# Adafruit_1_3in_128x64_STEMMA_QT.net
KiCad netlist of a schematic drawn in EAGLE
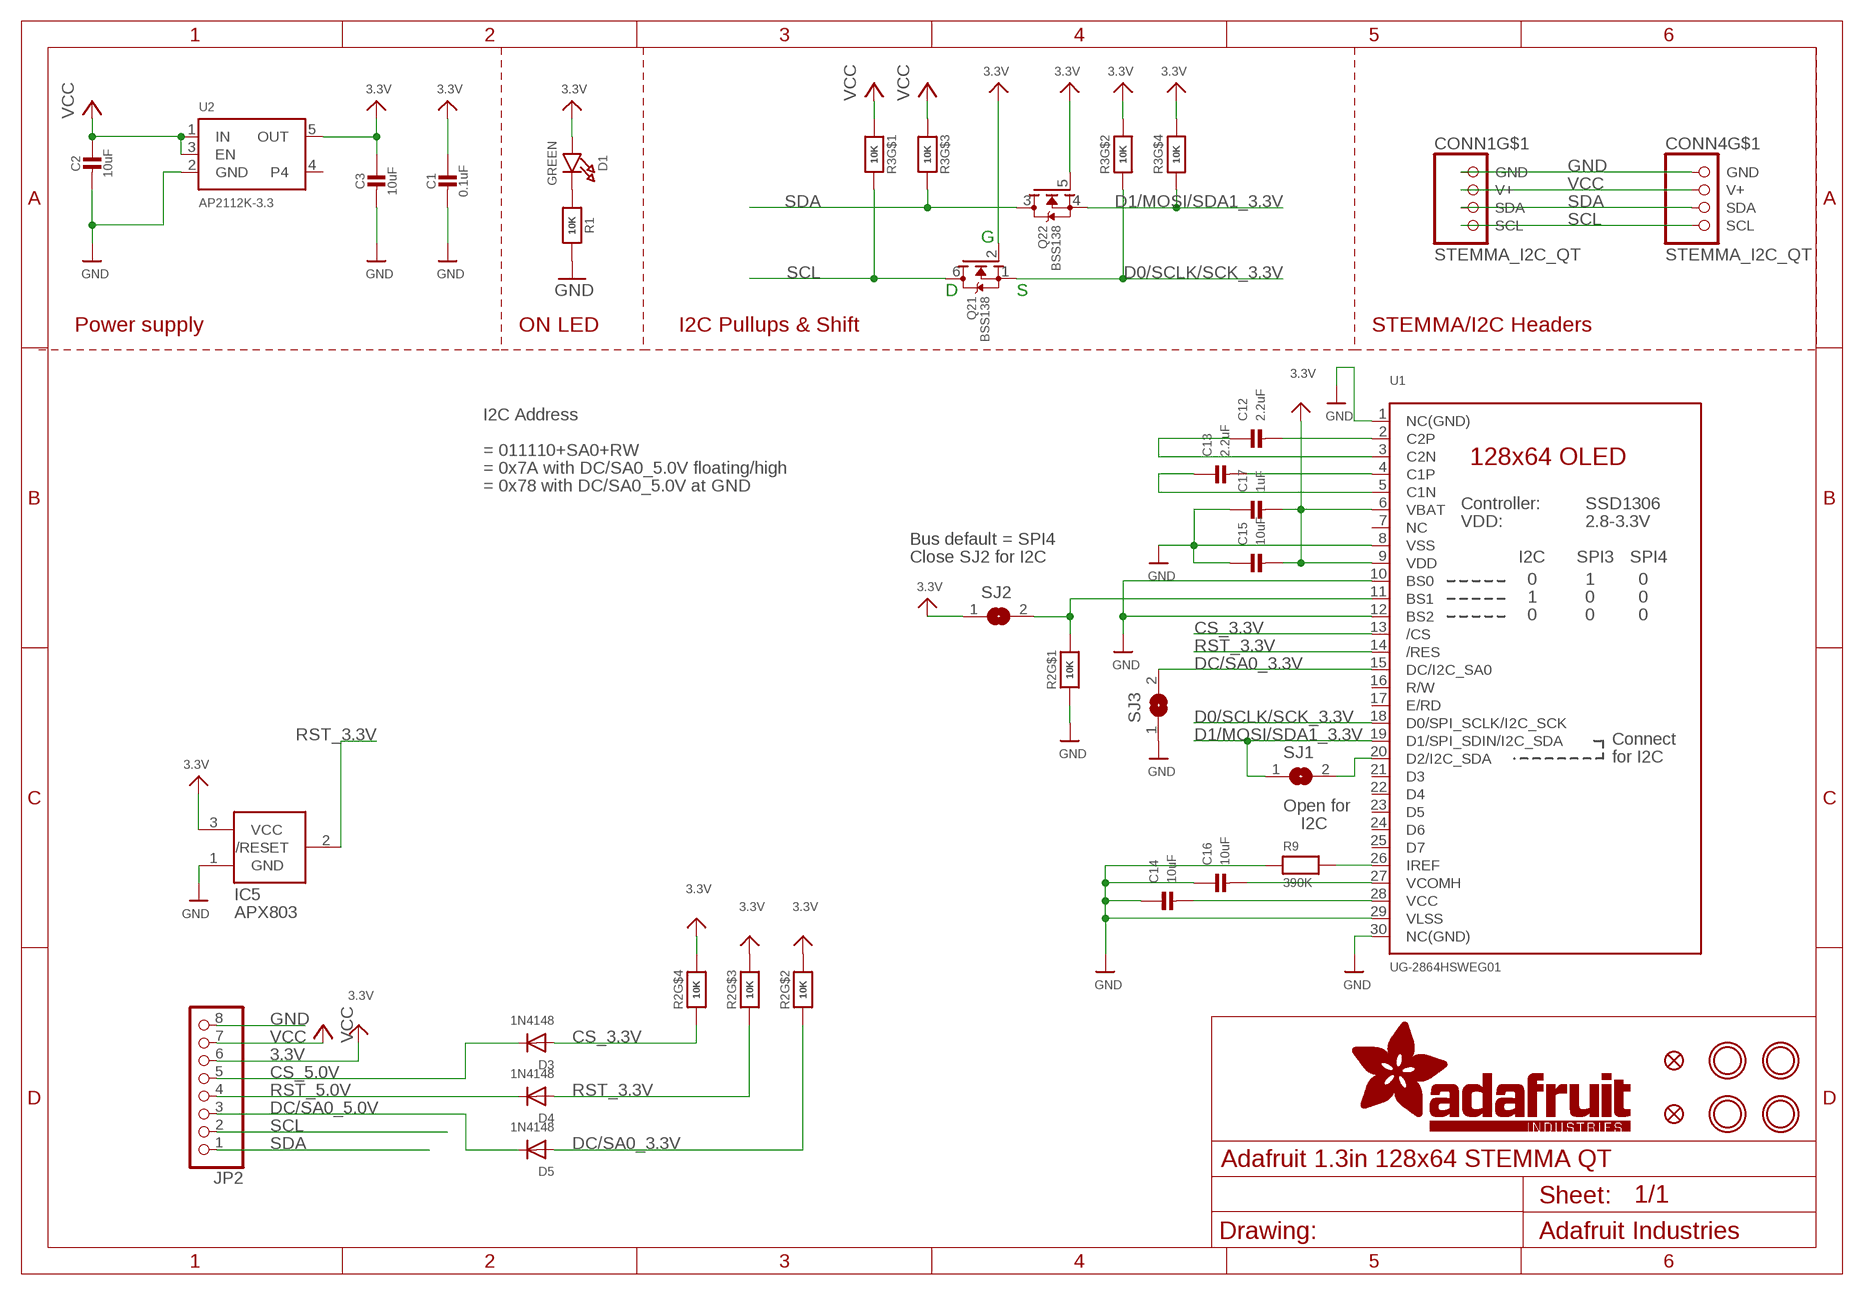
[diagram p0: schematic, sheet 1]

(export (version "E")
  (design (tool "Eeschema 10.0.6"))
  (components
    (comp (ref "C1")
      (value "0.1uF")
      (footprint "eagle-import:0603-NO")
      (libsource (lib "eagle-import") (part "CAP_CERAMIC0603_NO"))
    )
    (comp (ref "C2")
      (value "10uF")
      (footprint "eagle-import:0805-NO")
      (libsource (lib "eagle-import") (part "CAP_CERAMIC0805-NOOUTLINE"))
    )
    (comp (ref "C3")
      (value "10uF")
      (footprint "eagle-import:0805-NO")
      (libsource (lib "eagle-import") (part "CAP_CERAMIC0805-NOOUTLINE"))
    )
    (comp (ref "C12")
      (value "2.2uF")
      (footprint "eagle-import:0805-NO")
      (libsource (lib "eagle-import") (part "CAP_CERAMIC0805-NOOUTLINE"))
    )
    (comp (ref "C13")
      (value "2.2uF")
      (footprint "eagle-import:0805-NO")
      (libsource (lib "eagle-import") (part "CAP_CERAMIC0805-NOOUTLINE"))
    )
    (comp (ref "C14")
      (value "10uF")
      (footprint "eagle-import:0805-NO")
      (libsource (lib "eagle-import") (part "CAP_CERAMIC0805-NOOUTLINE"))
    )
    (comp (ref "C15")
      (value "10uF")
      (footprint "eagle-import:0805-NO")
      (libsource (lib "eagle-import") (part "CAP_CERAMIC0805-NOOUTLINE"))
    )
    (comp (ref "C16")
      (value "10uF")
      (footprint "eagle-import:0805-NO")
      (libsource (lib "eagle-import") (part "CAP_CERAMIC0805-NOOUTLINE"))
    )
    (comp (ref "C17")
      (value "1uF")
      (footprint "eagle-import:0603-NO")
      (libsource (lib "eagle-import") (part "CAP_CERAMIC0603_NO"))
    )
    (comp (ref "CONN1")
      (value "STEMMA_I2C_QT")
      (footprint "eagle-import:JST_SH4")
      (libsource (lib "eagle-import") (part "STEMMA_I2C_QT"))
    )
    (comp (ref "CONN4")
      (value "STEMMA_I2C_QT")
      (footprint "eagle-import:JST_SH4")
      (libsource (lib "eagle-import") (part "STEMMA_I2C_QT"))
    )
    (comp (ref "D1")
      (value "GREEN")
      (footprint "eagle-import:CHIPLED_0603_NOOUTLINE")
      (libsource (lib "eagle-import") (part "LED0603_NOOUTLINE"))
    )
    (comp (ref "D3")
      (value "1N4148")
      (footprint "eagle-import:SOD-323")
      (libsource (lib "eagle-import") (part "DIODESOD-323"))
    )
    (comp (ref "D4")
      (value "1N4148")
      (footprint "eagle-import:SOD-323")
      (libsource (lib "eagle-import") (part "DIODESOD-323"))
    )
    (comp (ref "D5")
      (value "1N4148")
      (footprint "eagle-import:SOD-323")
      (libsource (lib "eagle-import") (part "DIODESOD-323"))
    )
    (comp (ref "FID3")
      (value "FIDUCIAL_1MM")
      (footprint "eagle-import:FIDUCIAL_1MM")
      (libsource (lib "eagle-import") (part "FIDUCIAL_1MM"))
    )
    (comp (ref "FID4")
      (value "FIDUCIAL_1MM")
      (footprint "eagle-import:FIDUCIAL_1MM")
      (libsource (lib "eagle-import") (part "FIDUCIAL_1MM"))
    )
    (comp (ref "IC5")
      (value "APX803")
      (footprint "eagle-import:SOT23")
      (libsource (lib "eagle-import") (part "AXP083-SAG"))
    )
    (comp (ref "JP2")
      (value "HEADER-1X870MIL")
      (footprint "eagle-import:1X08_ROUND_70")
      (libsource (lib "eagle-import") (part "HEADER-1X870MIL"))
    )
    (comp (ref "Q2")
      (value "BSS138")
      (footprint "eagle-import:SOT363")
      (libsource (lib "eagle-import") (part "MOSFET-N_DUAL"))
    )
    (comp (ref "R1")
      (value "10K")
      (footprint "eagle-import:0603-NO")
      (libsource (lib "eagle-import") (part "RESISTOR_0603_NOOUT"))
    )
    (comp (ref "R2")
      (value "10K")
      (footprint "eagle-import:RESPACK_4X0603")
      (libsource (lib "eagle-import") (part "RESISTOR_4PACK"))
    )
    (comp (ref "R3")
      (value "10K")
      (footprint "eagle-import:RESPACK_4X0603")
      (libsource (lib "eagle-import") (part "RESISTOR_4PACK"))
    )
    (comp (ref "R9")
      (value "390K")
      (footprint "eagle-import:0603-NO")
      (libsource (lib "eagle-import") (part "RESISTOR_0603_NOOUT"))
    )
    (comp (ref "SJ1")
      (value "SOLDERJUMPERCLOSED")
      (footprint "eagle-import:SOLDERJUMPER_CLOSEDWIRE")
      (libsource (lib "eagle-import") (part "SOLDERJUMPERCLOSED"))
    )
    (comp (ref "SJ2")
      (value "SOLDERJUMPERCLOSED")
      (footprint "eagle-import:SOLDERJUMPER_CLOSEDWIRE")
      (libsource (lib "eagle-import") (part "SOLDERJUMPERCLOSED"))
    )
    (comp (ref "SJ3")
      (value "SOLDERJUMPER")
      (footprint "eagle-import:SOLDERJUMPER_ARROW_NOPASTE")
      (libsource (lib "eagle-import") (part "SOLDERJUMPER"))
    )
    (comp (ref "U$1")
      (value "MOUNTINGHOLE2.5")
      (footprint "eagle-import:MOUNTINGHOLE_2.5_PLATED")
      (libsource (lib "eagle-import") (part "MOUNTINGHOLE2.5"))
    )
    (comp (ref "U$17")
      (value "MOUNTINGHOLE2.5")
      (footprint "eagle-import:MOUNTINGHOLE_2.5_PLATED")
      (libsource (lib "eagle-import") (part "MOUNTINGHOLE2.5"))
    )
    (comp (ref "U$19")
      (value "MOUNTINGHOLE2.5")
      (footprint "eagle-import:MOUNTINGHOLE_2.5_PLATED")
      (libsource (lib "eagle-import") (part "MOUNTINGHOLE2.5"))
    )
    (comp (ref "U$21")
      (value "MOUNTINGHOLE2.5")
      (footprint "eagle-import:MOUNTINGHOLE_2.5_PLATED")
      (libsource (lib "eagle-import") (part "MOUNTINGHOLE2.5"))
    )
    (comp (ref "U1")
      (value "UG-2864HSWEG01")
      (footprint "eagle-import:UG-2864HSWEG01_1.3_WRAPAROUND")
      (libsource (lib "eagle-import") (part "DISP_OLED_UG-2864HSWEG01"))
    )
    (comp (ref "U2")
      (value "AP2112K-3.3")
      (footprint "eagle-import:SOT23-5")
      (libsource (lib "eagle-import") (part "VREG_SOT23-5"))
    )
  )
  (nets
    (net (code "1") (name "/CS_3.3V") (class "Default")
      (node (ref "D3") (pin "A") (pinfunction "A_A") (pintype "passive"))
      (node (ref "R2") (pin "4") (pinfunction "1_4") (pintype "passive"))
      (node (ref "U1") (pin "13") (pinfunction "/CS_13") (pintype "input"))
    )
    (net (code "2") (name "/CS_5.0V") (class "Default")
      (node (ref "D3") (pin "C") (pinfunction "C_C") (pintype "passive"))
      (node (ref "JP2") (pin "5") (pinfunction "5_5") (pintype "passive"))
    )
    (net (code "3") (name "/D0{slash}SCLK{slash}SCK_3.3V") (class "Default")
      (node (ref "Q2") (pin "1") (pinfunction "S_1") (pintype "bidirectional"))
      (node (ref "R3") (pin "7") (pinfunction "2_7") (pintype "passive"))
      (node (ref "U1") (pin "18") (pinfunction "D0/SPI_SCLK/I2C_SCK_18") (pintype "bidirectional"))
    )
    (net (code "4") (name "/D1{slash}MOSI{slash}SDA1_3.3V") (class "Default")
      (node (ref "Q2") (pin "4") (pinfunction "S_4") (pintype "bidirectional"))
      (node (ref "R3") (pin "5") (pinfunction "2_5") (pintype "passive"))
      (node (ref "SJ1") (pin "1") (pinfunction "1_1") (pintype "passive"))
      (node (ref "U1") (pin "19") (pinfunction "D1/SPI_SDIN/I2C_SDA_19") (pintype "bidirectional"))
    )
    (net (code "5") (name "/DC{slash}SA0_3.3V") (class "Default")
      (node (ref "D5") (pin "A") (pinfunction "A_A") (pintype "passive"))
      (node (ref "R2") (pin "2") (pinfunction "1_2") (pintype "passive"))
      (node (ref "SJ3") (pin "2") (pinfunction "2_2") (pintype "passive"))
      (node (ref "U1") (pin "15") (pinfunction "DC/I2C_SA0_15") (pintype "input"))
    )
    (net (code "6") (name "/DC{slash}SA0_5.0V") (class "Default")
      (node (ref "D5") (pin "C") (pinfunction "C_C") (pintype "passive"))
      (node (ref "JP2") (pin "3") (pinfunction "3_3") (pintype "passive"))
    )
    (net (code "7") (name "/RST_3.3V") (class "Default")
      (node (ref "D4") (pin "A") (pinfunction "A_A") (pintype "passive"))
      (node (ref "IC5") (pin "2") (pinfunction "/RESET_2") (pintype "output"))
      (node (ref "R2") (pin "3") (pinfunction "1_3") (pintype "passive"))
      (node (ref "U1") (pin "14") (pinfunction "/RES_14") (pintype "input"))
    )
    (net (code "8") (name "/RST_5.0V") (class "Default")
      (node (ref "D4") (pin "C") (pinfunction "C_C") (pintype "passive"))
      (node (ref "JP2") (pin "4") (pinfunction "4_4") (pintype "passive"))
    )
    (net (code "9") (name "/SCL") (class "Default")
      (node (ref "CONN1") (pin "4") (pinfunction "SCL_4") (pintype "passive"))
      (node (ref "CONN4") (pin "4") (pinfunction "SCL_4") (pintype "passive"))
      (node (ref "JP2") (pin "2") (pinfunction "2_2") (pintype "passive"))
      (node (ref "Q2") (pin "6") (pinfunction "D_6") (pintype "bidirectional"))
      (node (ref "R3") (pin "8") (pinfunction "2_8") (pintype "passive"))
    )
    (net (code "10") (name "/SDA") (class "Default")
      (node (ref "CONN1") (pin "3") (pinfunction "SDA_3") (pintype "passive"))
      (node (ref "CONN4") (pin "3") (pinfunction "SDA_3") (pintype "passive"))
      (node (ref "JP2") (pin "1") (pinfunction "1_1") (pintype "passive"))
      (node (ref "Q2") (pin "3") (pinfunction "D_3") (pintype "bidirectional"))
      (node (ref "R3") (pin "6") (pinfunction "2_6") (pintype "passive"))
    )
    (net (code "11") (name "3.3V") (class "Default")
      (node (ref "C1") (pin "1") (pinfunction "1_1") (pintype "passive"))
      (node (ref "C15") (pin "2") (pinfunction "2_2") (pintype "passive"))
      (node (ref "C17") (pin "2") (pinfunction "2_2") (pintype "passive"))
      (node (ref "C3") (pin "1") (pinfunction "1_1") (pintype "passive"))
      (node (ref "D1") (pin "A") (pinfunction "A_A") (pintype "passive"))
      (node (ref "IC5") (pin "3") (pinfunction "VCC_3") (pintype "power_in"))
      (node (ref "JP2") (pin "6") (pinfunction "6_6") (pintype "passive"))
      (node (ref "Q2") (pin "2") (pinfunction "G_2") (pintype "bidirectional"))
      (node (ref "Q2") (pin "5") (pinfunction "G_5") (pintype "bidirectional"))
      (node (ref "R2") (pin "5") (pinfunction "2_5") (pintype "passive"))
      (node (ref "R2") (pin "6") (pinfunction "2_6") (pintype "passive"))
      (node (ref "R2") (pin "7") (pinfunction "2_7") (pintype "passive"))
      (node (ref "R3") (pin "2") (pinfunction "1_2") (pintype "passive"))
      (node (ref "R3") (pin "4") (pinfunction "1_4") (pintype "passive"))
      (node (ref "SJ2") (pin "1") (pinfunction "1_1") (pintype "passive"))
      (node (ref "U1") (pin "6") (pinfunction "VBAT_6") (pintype "input"))
      (node (ref "U1") (pin "9") (pinfunction "VDD_9") (pintype "power_in"))
      (node (ref "U2") (pin "5") (pinfunction "OUT_5") (pintype "power_in"))
    )
    (net (code "12") (name "GND") (class "Default")
      (node (ref "C1") (pin "2") (pinfunction "2_2") (pintype "passive"))
      (node (ref "C14") (pin "1") (pinfunction "1_1") (pintype "passive"))
      (node (ref "C15") (pin "1") (pinfunction "1_1") (pintype "passive"))
      (node (ref "C16") (pin "1") (pinfunction "1_1") (pintype "passive"))
      (node (ref "C17") (pin "1") (pinfunction "1_1") (pintype "passive"))
      (node (ref "C2") (pin "2") (pinfunction "2_2") (pintype "passive"))
      (node (ref "C3") (pin "2") (pinfunction "2_2") (pintype "passive"))
      (node (ref "CONN1") (pin "1") (pinfunction "GND_1") (pintype "passive"))
      (node (ref "CONN4") (pin "1") (pinfunction "GND_1") (pintype "passive"))
      (node (ref "IC5") (pin "1") (pinfunction "GND_1") (pintype "power_in"))
      (node (ref "JP2") (pin "8") (pinfunction "8_8") (pintype "passive"))
      (node (ref "R1") (pin "2") (pinfunction "2_2") (pintype "passive"))
      (node (ref "R2") (pin "1") (pinfunction "1_1") (pintype "passive"))
      (node (ref "R9") (pin "1") (pinfunction "1_1") (pintype "passive"))
      (node (ref "SJ3") (pin "1") (pinfunction "1_1") (pintype "passive"))
      (node (ref "U1") (pin "1") (pinfunction "NC(GND)_1") (pintype "input"))
      (node (ref "U1") (pin "10") (pinfunction "BS0_10") (pintype "input"))
      (node (ref "U1") (pin "12") (pinfunction "BS2_12") (pintype "input"))
      (node (ref "U1") (pin "29") (pinfunction "VLSS_29") (pintype "power_in"))
      (node (ref "U1") (pin "30") (pinfunction "NC(GND)_30") (pintype "input"))
      (node (ref "U1") (pin "8") (pinfunction "VSS_8") (pintype "power_in"))
      (node (ref "U2") (pin "2") (pinfunction "GND_2") (pintype "power_in"))
    )
    (net (code "13") (name "Net-(D1-PadC)") (class "Default")
      (node (ref "D1") (pin "C") (pinfunction "C_C") (pintype "passive"))
      (node (ref "R1") (pin "1") (pinfunction "1_1") (pintype "passive"))
    )
    (net (code "14") (name "Net-(R2A-2)") (class "Default")
      (node (ref "R2") (pin "8") (pinfunction "2_8") (pintype "passive"))
      (node (ref "SJ2") (pin "2") (pinfunction "2_2") (pintype "passive"))
      (node (ref "U1") (pin "11") (pinfunction "BS1_11") (pintype "input"))
    )
    (net (code "15") (name "Net-(U1-C1N)") (class "Default")
      (node (ref "C13") (pin "1") (pinfunction "1_1") (pintype "passive"))
      (node (ref "U1") (pin "5") (pinfunction "C1N_5") (pintype "input"))
    )
    (net (code "16") (name "Net-(U1-C1P)") (class "Default")
      (node (ref "C13") (pin "2") (pinfunction "2_2") (pintype "passive"))
      (node (ref "U1") (pin "4") (pinfunction "C1P_4") (pintype "input"))
    )
    (net (code "17") (name "Net-(U1-C2N)") (class "Default")
      (node (ref "C12") (pin "1") (pinfunction "1_1") (pintype "passive"))
      (node (ref "U1") (pin "3") (pinfunction "C2N_3") (pintype "input"))
    )
    (net (code "18") (name "Net-(U1-C2P)") (class "Default")
      (node (ref "C12") (pin "2") (pinfunction "2_2") (pintype "passive"))
      (node (ref "U1") (pin "2") (pinfunction "C2P_2") (pintype "input"))
    )
    (net (code "19") (name "Net-(U1-D2{slash}I2C_SDA)") (class "Default")
      (node (ref "SJ1") (pin "2") (pinfunction "2_2") (pintype "passive"))
      (node (ref "U1") (pin "20") (pinfunction "D2/I2C_SDA_20") (pintype "bidirectional"))
    )
    (net (code "20") (name "Net-(U1-IREF)") (class "Default")
      (node (ref "R9") (pin "2") (pinfunction "2_2") (pintype "passive"))
      (node (ref "U1") (pin "26") (pinfunction "IREF_26") (pintype "input"))
    )
    (net (code "21") (name "Net-(U1-VCC)") (class "Default")
      (node (ref "C14") (pin "2") (pinfunction "2_2") (pintype "passive"))
      (node (ref "U1") (pin "28") (pinfunction "VCC_28") (pintype "power_in"))
    )
    (net (code "22") (name "Net-(U1-VCOMH)") (class "Default")
      (node (ref "C16") (pin "2") (pinfunction "2_2") (pintype "passive"))
      (node (ref "U1") (pin "27") (pinfunction "VCOMH_27") (pintype "output"))
    )
    (net (code "23") (name "VCC") (class "Default")
      (node (ref "C2") (pin "1") (pinfunction "1_1") (pintype "passive"))
      (node (ref "CONN1") (pin "2") (pinfunction "V+_2") (pintype "passive"))
      (node (ref "CONN4") (pin "2") (pinfunction "V+_2") (pintype "passive"))
      (node (ref "JP2") (pin "7") (pinfunction "7_7") (pintype "passive"))
      (node (ref "R3") (pin "1") (pinfunction "1_1") (pintype "passive"))
      (node (ref "R3") (pin "3") (pinfunction "1_3") (pintype "passive"))
      (node (ref "U2") (pin "1") (pinfunction "IN_1") (pintype "power_in"))
      (node (ref "U2") (pin "3") (pinfunction "EN_3") (pintype "input"))
    )
    (net (code "24") (name "unconnected-(U1-D3-Pad21)") (class "Default")
      (node (ref "U1") (pin "21") (pinfunction "D3_21") (pintype "bidirectional"))
    )
    (net (code "25") (name "unconnected-(U1-D4-Pad22)") (class "Default")
      (node (ref "U1") (pin "22") (pinfunction "D4_22") (pintype "bidirectional"))
    )
    (net (code "26") (name "unconnected-(U1-D5-Pad23)") (class "Default")
      (node (ref "U1") (pin "23") (pinfunction "D5_23") (pintype "bidirectional"))
    )
    (net (code "27") (name "unconnected-(U1-D6-Pad24)") (class "Default")
      (node (ref "U1") (pin "24") (pinfunction "D6_24") (pintype "bidirectional"))
    )
    (net (code "28") (name "unconnected-(U1-D7-Pad25)") (class "Default")
      (node (ref "U1") (pin "25") (pinfunction "D7_25") (pintype "bidirectional"))
    )
    (net (code "29") (name "unconnected-(U1-E{slash}RD-Pad17)") (class "Default")
      (node (ref "U1") (pin "17") (pinfunction "E/RD_17") (pintype "input"))
    )
    (net (code "30") (name "unconnected-(U1-NC-Pad7)") (class "Default")
      (node (ref "U1") (pin "7") (pinfunction "NC_7") (pintype "no_connect"))
    )
    (net (code "31") (name "unconnected-(U1-R{slash}W-Pad16)") (class "Default")
      (node (ref "U1") (pin "16") (pinfunction "R/W_16") (pintype "input"))
    )
    (net (code "32") (name "unconnected-(U2-P4-Pad4)") (class "Default")
      (node (ref "U2") (pin "4") (pinfunction "P4_4") (pintype "bidirectional"))
    )
  )
)
